# DS157-1_1-B.net
KiCad netlist of a schematic drawn in Altium Designer
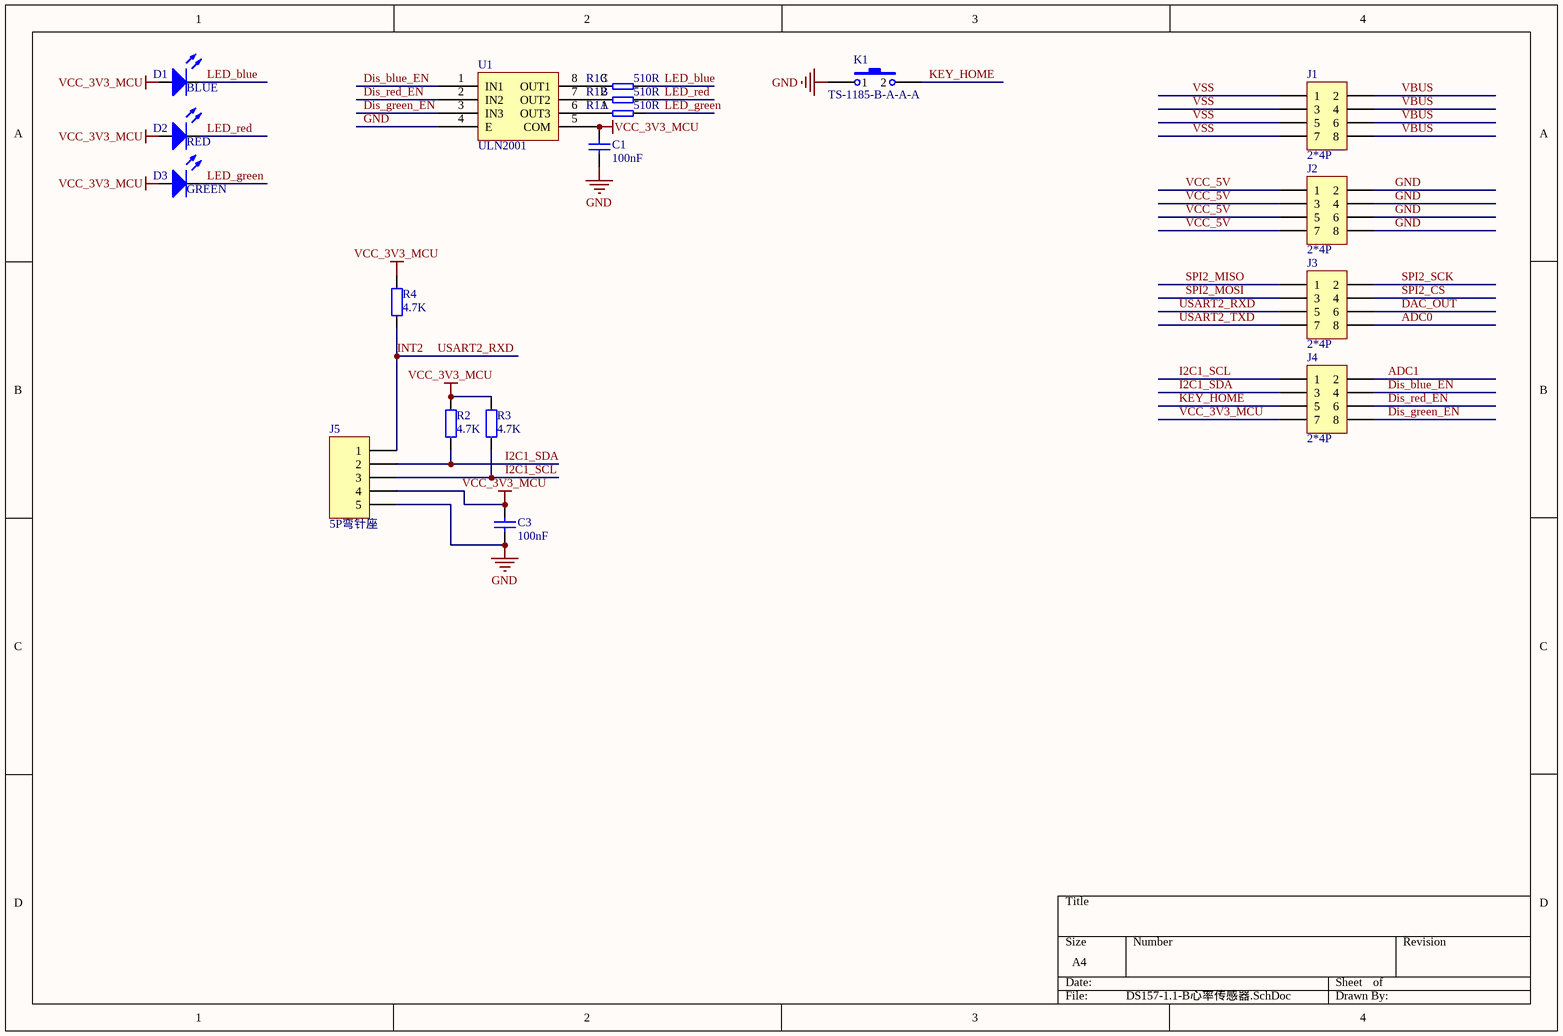
[diagram p0: DS157-1.1-B心率传感器.SchDoc]

(export (version "E")
  (design (tool "Eeschema 10.0.6"))
  (components
    (comp (ref "C1")
      (value "100nF")
      (footprint "0603CAP")
      (description "贴片电容")
      (fields (field (name "Comment") "SMDCAP00013"))
      (libsource (lib "AD_SCH") (part "MLCC 100nF 50V ±10％ 0603"))
    )
    (comp (ref "C3")
      (value "100nF")
      (footprint "0603CAP")
      (description "贴片电容")
      (fields (field (name "Comment") "SMDCAP00013"))
      (libsource (lib "AD_SCH") (part "MLCC 100nF 50V ±10％ 0603"))
    )
    (comp (ref "D1")
      (value "BLUE")
      (footprint "LED_0805")
      (description "贴片LED")
      (fields (field (name "Comment") "SMDLED00010"))
      (libsource (lib "AD_SCH") (part "Chip 蓝色LED 0805"))
    )
    (comp (ref "D2")
      (value "RED")
      (footprint "LED_0805")
      (description "贴片LED")
      (fields (field (name "Comment") "SMDLED00003"))
      (libsource (lib "AD_SCH") (part "Chip 红色LED 0805"))
    )
    (comp (ref "D3")
      (value "GREEN")
      (footprint "LED_0805")
      (description "贴片LED")
      (fields (field (name "Comment") "Chip 翠绿LED 0805"))
      (libsource (lib "AD_SCH") (part "Chip 翠绿LED 0805"))
    )
    (comp (ref "J1")
      (value "2*4P")
      (footprint "X1321WVS-2x04J-C40D53")
      (description "双排针2x4P 立贴 1.27mm")
      (fields (field (name "Comment") "X1321WVS-2x04J-C40D53"))
      (libsource (lib "AD_SCH") (part "X1321WVS-2x04J-C40D53"))
    )
    (comp (ref "J2")
      (value "2*4P")
      (footprint "X1321WVS-2x04J-C40D53")
      (description "双排针2x4P 立贴 1.27mm")
      (fields (field (name "Comment") "X1321WVS-2x04J-C40D53"))
      (libsource (lib "AD_SCH") (part "X1321WVS-2x04J-C40D53"))
    )
    (comp (ref "J3")
      (value "2*4P")
      (footprint "X1321WVS-2x04J-C40D53")
      (description "双排针2x4P 立贴 1.27mm")
      (fields (field (name "Comment") "X1321WVS-2x04J-C40D53"))
      (libsource (lib "AD_SCH") (part "X1321WVS-2x04J-C40D53"))
    )
    (comp (ref "J4")
      (value "2*4P")
      (footprint "X1321WVS-2x04J-C40D53")
      (description "双排针2x4P 立贴 1.27mm")
      (fields (field (name "Comment") "X1321WVS-2x04J-C40D53"))
      (libsource (lib "AD_SCH") (part "X1321WVS-2x04J-C40D53"))
    )
    (comp (ref "J5")
      (value "5P弯针座")
      (footprint "XH2.54-5PW")
      (fields (field (name "Comment") "SL000000035"))
      (libsource (lib "AD_SCH") (part "XH2.54mm-5AW 弯针座"))
    )
    (comp (ref "K1")
      (value "TS-1185-B-A-A-A")
      (footprint "KEY_TS-1185-x-A-A-A")
      (description "轻触开关")
      (libsource (lib "AD_SCH") (part "TS-1185-B-A-A-A"))
    )
    (comp (ref "R1")
      (value "510R")
      (footprint "0603RES_Pack4")
      (description "贴片排阻")
      (fields (field (name "Comment") "SMDRES05003"))
      (libsource (lib "AD_SCH") (part "Chip R*4 510R 1/16W ±5％ 0603"))
    )
    (comp (ref "R2")
      (value "4.7K")
      (footprint "0603RES")
      (description "贴片电阻")
      (fields (field (name "Comment") "SMDRES00047"))
      (libsource (lib "AD_SCH") (part "Chip 4.7K 1/16W ±1％ 0603"))
    )
    (comp (ref "R3")
      (value "4.7K")
      (footprint "0603RES")
      (description "贴片电阻")
      (fields (field (name "Comment") "SMDRES00047"))
      (libsource (lib "AD_SCH") (part "Chip 4.7K 1/16W ±1％ 0603"))
    )
    (comp (ref "R4")
      (value "4.7K")
      (footprint "0603RES")
      (description "贴片电阻")
      (fields (field (name "Comment") "SMDRES00047"))
      (libsource (lib "AD_SCH") (part "Chip 4.7K 1/16W ±1％ 0603"))
    )
    (comp (ref "U1")
      (value "ULN2001")
      (footprint "SO-8")
      (description "电机驱动芯片")
      (fields (field (name "Comment") "SMDIC000018"))
      (libsource (lib "AD_SCH") (part "ULN2001 SOP-8"))
    )
  )
  (nets
    (net (code "1") (name "/ADC0") (class "Default")
      (node (ref "J3") (pin "8") (pinfunction "8_8") (pintype "passive"))
    )
    (net (code "2") (name "/ADC1") (class "Default")
      (node (ref "J4") (pin "2") (pinfunction "2_2") (pintype "passive"))
    )
    (net (code "3") (name "/DAC_OUT") (class "Default")
      (node (ref "J3") (pin "6") (pinfunction "6_6") (pintype "passive"))
    )
    (net (code "4") (name "/Dis_blue_EN") (class "Default")
      (node (ref "J4") (pin "4") (pinfunction "4_4") (pintype "passive"))
      (node (ref "U1") (pin "1") (pinfunction "IN1_1") (pintype "passive"))
    )
    (net (code "5") (name "/Dis_green_EN") (class "Default")
      (node (ref "J4") (pin "8") (pinfunction "8_8") (pintype "passive"))
      (node (ref "U1") (pin "3") (pinfunction "IN3_3") (pintype "passive"))
    )
    (net (code "6") (name "/Dis_red_EN") (class "Default")
      (node (ref "J4") (pin "6") (pinfunction "6_6") (pintype "passive"))
      (node (ref "U1") (pin "2") (pinfunction "IN2_2") (pintype "passive"))
    )
    (net (code "7") (name "/I2C1_SCL") (class "Default")
      (node (ref "J4") (pin "1") (pinfunction "1_1") (pintype "passive"))
      (node (ref "J5") (pin "3") (pinfunction "3_3") (pintype "passive"))
      (node (ref "R3") (pin "1") (pinfunction "1_1") (pintype "passive"))
    )
    (net (code "8") (name "/I2C1_SDA") (class "Default")
      (node (ref "J4") (pin "3") (pinfunction "3_3") (pintype "passive"))
      (node (ref "J5") (pin "2") (pinfunction "2_2") (pintype "passive"))
      (node (ref "R2") (pin "1") (pinfunction "1_1") (pintype "passive"))
    )
    (net (code "9") (name "/INT2") (class "Default")
      (node (ref "J3") (pin "5") (pinfunction "5_5") (pintype "passive"))
      (node (ref "J5") (pin "1") (pinfunction "1_1") (pintype "passive"))
      (node (ref "R4") (pin "1") (pinfunction "1_1") (pintype "passive"))
    )
    (net (code "10") (name "/KEY_HOME") (class "Default")
      (node (ref "J4") (pin "5") (pinfunction "5_5") (pintype "passive"))
      (node (ref "K1") (pin "2") (pinfunction "2_2") (pintype "passive"))
    )
    (net (code "11") (name "/LED_blue") (class "Default")
      (node (ref "D1") (pin "2") (pinfunction "K_2") (pintype "passive"))
      (node (ref "R1") (pin "6") (pinfunction "6_6") (pintype "passive"))
    )
    (net (code "12") (name "/LED_green") (class "Default")
      (node (ref "D3") (pin "2") (pinfunction "K_2") (pintype "passive"))
      (node (ref "R1") (pin "8") (pinfunction "8_8") (pintype "passive"))
    )
    (net (code "13") (name "/LED_red") (class "Default")
      (node (ref "D2") (pin "2") (pinfunction "K_2") (pintype "passive"))
      (node (ref "R1") (pin "7") (pinfunction "7_7") (pintype "passive"))
    )
    (net (code "14") (name "/SPI2_CS") (class "Default")
      (node (ref "J3") (pin "4") (pinfunction "4_4") (pintype "passive"))
    )
    (net (code "15") (name "/SPI2_MISO") (class "Default")
      (node (ref "J3") (pin "1") (pinfunction "1_1") (pintype "passive"))
    )
    (net (code "16") (name "/SPI2_MOSI") (class "Default")
      (node (ref "J3") (pin "3") (pinfunction "3_3") (pintype "passive"))
    )
    (net (code "17") (name "/SPI2_SCK") (class "Default")
      (node (ref "J3") (pin "2") (pinfunction "2_2") (pintype "passive"))
    )
    (net (code "18") (name "/USART2_TXD") (class "Default")
      (node (ref "J3") (pin "7") (pinfunction "7_7") (pintype "passive"))
    )
    (net (code "19") (name "/VBUS") (class "Default")
      (node (ref "J1") (pin "2") (pinfunction "2_2") (pintype "passive"))
      (node (ref "J1") (pin "4") (pinfunction "4_4") (pintype "passive"))
      (node (ref "J1") (pin "6") (pinfunction "6_6") (pintype "passive"))
      (node (ref "J1") (pin "8") (pinfunction "8_8") (pintype "passive"))
    )
    (net (code "20") (name "/VCC_5V") (class "Default")
      (node (ref "J2") (pin "1") (pinfunction "1_1") (pintype "passive"))
      (node (ref "J2") (pin "3") (pinfunction "3_3") (pintype "passive"))
      (node (ref "J2") (pin "5") (pinfunction "5_5") (pintype "passive"))
      (node (ref "J2") (pin "7") (pinfunction "7_7") (pintype "passive"))
    )
    (net (code "21") (name "/VSS") (class "Default")
      (node (ref "J1") (pin "1") (pinfunction "1_1") (pintype "passive"))
      (node (ref "J1") (pin "3") (pinfunction "3_3") (pintype "passive"))
      (node (ref "J1") (pin "5") (pinfunction "5_5") (pintype "passive"))
      (node (ref "J1") (pin "7") (pinfunction "7_7") (pintype "passive"))
    )
    (net (code "22") (name "GND") (class "Default")
      (node (ref "C1") (pin "1") (pinfunction "1_1") (pintype "passive"))
      (node (ref "C3") (pin "1") (pinfunction "1_1") (pintype "passive"))
      (node (ref "J2") (pin "2") (pinfunction "2_2") (pintype "passive"))
      (node (ref "J2") (pin "4") (pinfunction "4_4") (pintype "passive"))
      (node (ref "J2") (pin "6") (pinfunction "6_6") (pintype "passive"))
      (node (ref "J2") (pin "8") (pinfunction "8_8") (pintype "passive"))
      (node (ref "J5") (pin "5") (pinfunction "5_5") (pintype "passive"))
      (node (ref "K1") (pin "1") (pinfunction "1_1") (pintype "passive"))
      (node (ref "U1") (pin "4") (pinfunction "E_4") (pintype "passive"))
    )
    (net (code "23") (name "Net-(U1-OUT1)") (class "Default")
      (node (ref "R1") (pin "3") (pinfunction "3_3") (pintype "passive"))
      (node (ref "U1") (pin "8") (pinfunction "OUT1_8") (pintype "passive"))
    )
    (net (code "24") (name "Net-(U1-OUT2)") (class "Default")
      (node (ref "R1") (pin "2") (pinfunction "2_2") (pintype "passive"))
      (node (ref "U1") (pin "7") (pinfunction "OUT2_7") (pintype "passive"))
    )
    (net (code "25") (name "Net-(U1-OUT3)") (class "Default")
      (node (ref "R1") (pin "1") (pinfunction "1_1") (pintype "passive"))
      (node (ref "U1") (pin "6") (pinfunction "OUT3_6") (pintype "passive"))
    )
    (net (code "26") (name "VCC_3V3_MCU") (class "Default")
      (node (ref "C1") (pin "2") (pinfunction "2_2") (pintype "passive"))
      (node (ref "C3") (pin "2") (pinfunction "2_2") (pintype "passive"))
      (node (ref "D1") (pin "1") (pinfunction "A_1") (pintype "passive"))
      (node (ref "D2") (pin "1") (pinfunction "A_1") (pintype "passive"))
      (node (ref "D3") (pin "1") (pinfunction "A_1") (pintype "passive"))
      (node (ref "J4") (pin "7") (pinfunction "7_7") (pintype "passive"))
      (node (ref "J5") (pin "4") (pinfunction "4_4") (pintype "passive"))
      (node (ref "R2") (pin "2") (pinfunction "2_2") (pintype "passive"))
      (node (ref "R3") (pin "2") (pinfunction "2_2") (pintype "passive"))
      (node (ref "R4") (pin "2") (pinfunction "2_2") (pintype "passive"))
      (node (ref "U1") (pin "5") (pinfunction "COM_5") (pintype "passive"))
    )
  )
)
